# Balancing_V3.net
KiCad netlist of a schematic drawn in EAGLE
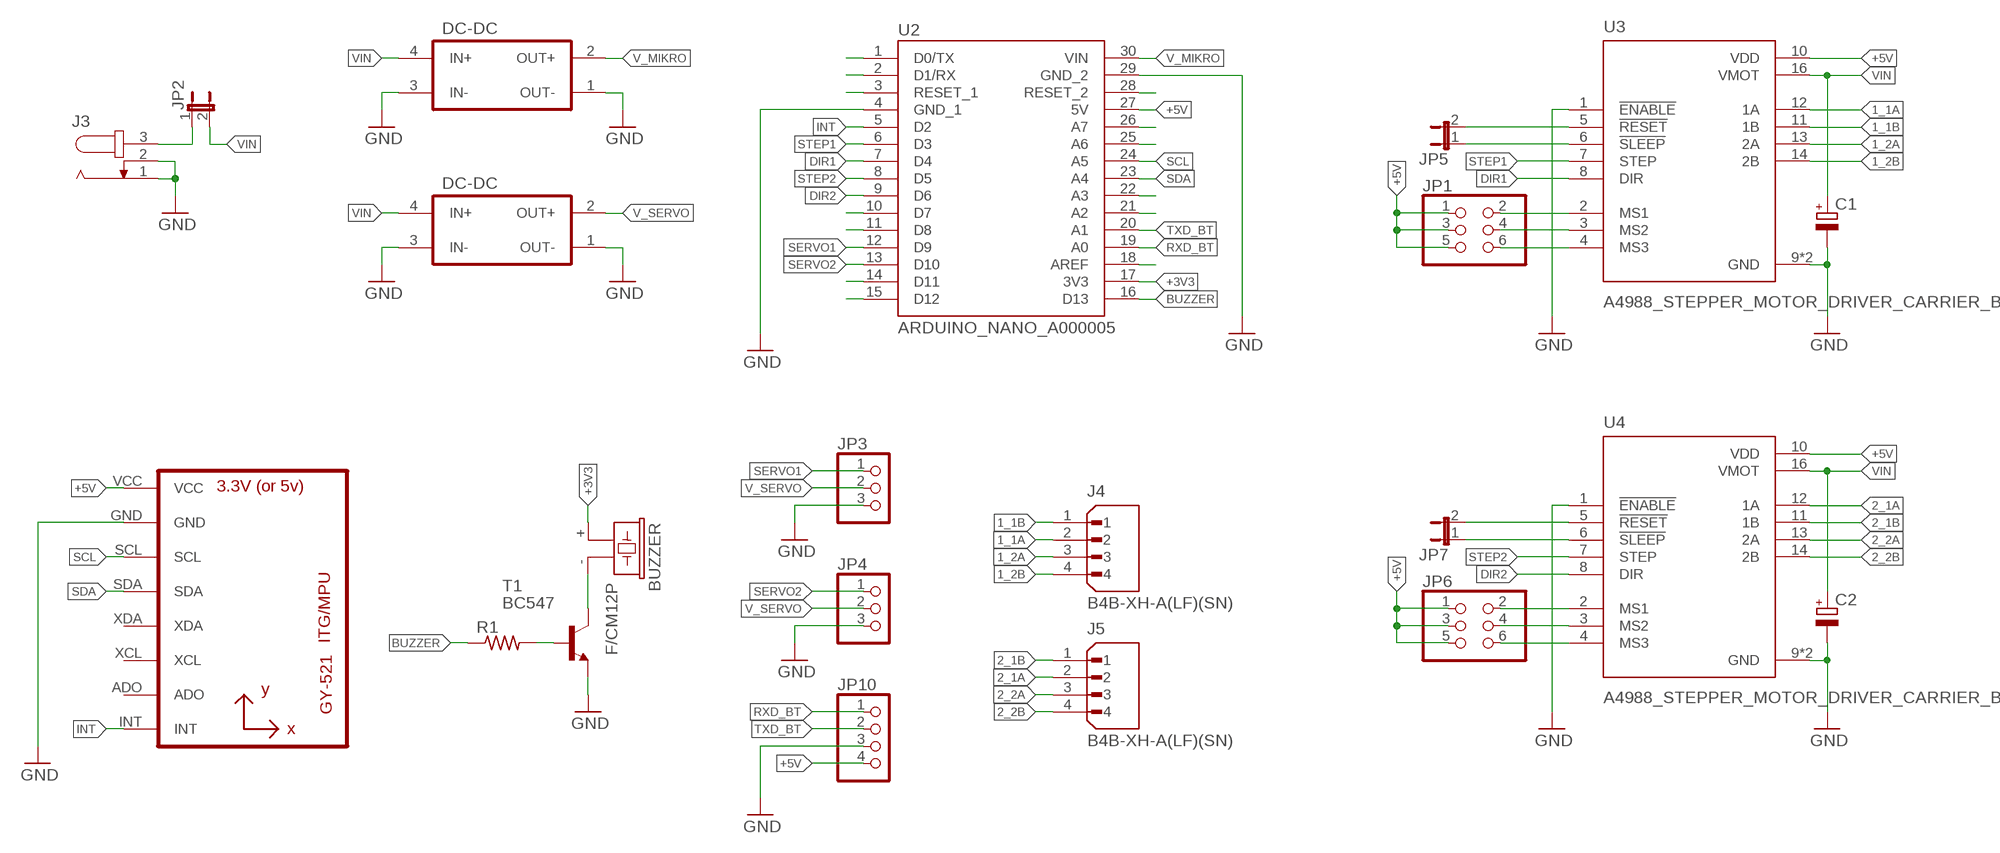
[diagram p0: schematic, sheet 1]

(export (version "E")
  (design (tool "Eeschema 10.0.6"))
  (components
    (comp (ref "BUZZER")
      (value "F/CM12P")
      (footprint "eagle-import:F_CM12P")
      (libsource (lib "eagle-import") (part "F/CM12P"))
    )
    (comp (ref "C1")
      (value "CPOL-EUE2.5-6")
      (footprint "eagle-import:E2,5-6")
      (libsource (lib "eagle-import") (part "CPOL-EUE2.5-6"))
    )
    (comp (ref "C2")
      (value "CPOL-EUE2.5-6")
      (footprint "eagle-import:E2,5-6")
      (libsource (lib "eagle-import") (part "CPOL-EUE2.5-6"))
    )
    (comp (ref "J3")
      (value "JACK-PLUG1")
      (footprint "eagle-import:SPC4078")
      (libsource (lib "eagle-import") (part "JACK-PLUG1"))
    )
    (comp (ref "J4")
      (value "B4B-XH-A(LF)(SN)")
      (footprint "eagle-import:JST_B4B-XH-A(LF)(SN)")
      (fields (field (name "MF") "JST") (field (name "MP") "B4B-XH-A  (LF)(SN)"))
      (libsource (lib "eagle-import") (part "B4B-XH-A(LF)(SN)"))
    )
    (comp (ref "J5")
      (value "B4B-XH-A(LF)(SN)")
      (footprint "eagle-import:JST_B4B-XH-A(LF)(SN)")
      (fields (field (name "MF") "JST") (field (name "MP") "B4B-XH-A  (LF)(SN)"))
      (libsource (lib "eagle-import") (part "B4B-XH-A(LF)(SN)"))
    )
    (comp (ref "JP1")
      (value "PINHD-2X3")
      (footprint "eagle-import:2X03")
      (libsource (lib "eagle-import") (part "PINHD-2X3"))
    )
    (comp (ref "JP2")
      (value "JP1E")
      (footprint "eagle-import:JP1")
      (libsource (lib "eagle-import") (part "JP1E"))
    )
    (comp (ref "JP3")
      (value "PINHD-1X3")
      (footprint "eagle-import:1X03")
      (libsource (lib "eagle-import") (part "PINHD-1X3"))
    )
    (comp (ref "JP4")
      (value "PINHD-1X3")
      (footprint "eagle-import:1X03")
      (libsource (lib "eagle-import") (part "PINHD-1X3"))
    )
    (comp (ref "JP5")
      (value "JP1E")
      (footprint "eagle-import:JP1")
      (libsource (lib "eagle-import") (part "JP1E"))
    )
    (comp (ref "JP6")
      (value "PINHD-2X3")
      (footprint "eagle-import:2X03")
      (libsource (lib "eagle-import") (part "PINHD-2X3"))
    )
    (comp (ref "JP7")
      (value "JP1E")
      (footprint "eagle-import:JP1")
      (libsource (lib "eagle-import") (part "JP1E"))
    )
    (comp (ref "JP10")
      (value "PINHD-1X4")
      (footprint "eagle-import:1X04")
      (libsource (lib "eagle-import") (part "PINHD-1X4"))
    )
    (comp (ref "R1")
      (value "R-US_0204/7")
      (footprint "eagle-import:0204_7")
      (libsource (lib "eagle-import") (part "R-US_0204/7"))
    )
    (comp (ref "T1")
      (value "BC547")
      (footprint "eagle-import:TO92")
      (libsource (lib "eagle-import") (part "BC547"))
    )
    (comp (ref "U$1")
      (value "DC-DC_CONV")
      (footprint "eagle-import:DC-DC_CONV")
      (libsource (lib "eagle-import") (part "DC-DC_CONV"))
    )
    (comp (ref "U$2")
      (value "DC-DC_CONV")
      (footprint "eagle-import:DC-DC_CONV")
      (libsource (lib "eagle-import") (part "DC-DC_CONV"))
    )
    (comp (ref "U1")
      (value "GY-521MPU6050")
      (footprint "eagle-import:GY-521")
      (libsource (lib "eagle-import") (part "GY-521MPU6050"))
    )
    (comp (ref "U2")
      (value "ARDUINO_NANO_A000005")
      (footprint "eagle-import:MODULE_ARDUINO_NANO_A000005")
      (fields (field (name "MF") "Arduino") (field (name "MP") "ARDUINO NANO A000005"))
      (libsource (lib "eagle-import") (part "ARDUINO_NANO_A000005"))
    )
    (comp (ref "U3")
      (value "A4988_STEPPER_MOTOR_DRIVER_CARRIER_BLACK")
      (footprint "eagle-import:MODULE_A4988_STEPPER_MOTOR_DRIVER_CARRIER_BLACK")
      (fields (field (name "MF") "Pololu") (field (name "MP") "A4988 STEPPER MOTOR DRIVER CARRIER BLACK"))
      (libsource (lib "eagle-import") (part "A4988_STEPPER_MOTOR_DRIVER_CARRIER_BLACK"))
    )
    (comp (ref "U4")
      (value "A4988_STEPPER_MOTOR_DRIVER_CARRIER_BLACK")
      (footprint "eagle-import:MODULE_A4988_STEPPER_MOTOR_DRIVER_CARRIER_BLACK")
      (fields (field (name "MF") "Pololu") (field (name "MP") "A4988 STEPPER MOTOR DRIVER CARRIER BLACK"))
      (libsource (lib "eagle-import") (part "A4988_STEPPER_MOTOR_DRIVER_CARRIER_BLACK"))
    )
  )
  (nets
    (net (code "1") (name "+3V3") (class "Default")
      (node (ref "BUZZER") (pin "+") (pinfunction "1_+") (pintype "passive"))
      (node (ref "U2") (pin "17") (pinfunction "3V3_17") (pintype "power_in"))
    )
    (net (code "2") (name "+5V") (class "Default")
      (node (ref "JP1") (pin "1") (pinfunction "1_1") (pintype "passive"))
      (node (ref "JP1") (pin "3") (pinfunction "3_3") (pintype "passive"))
      (node (ref "JP1") (pin "5") (pinfunction "5_5") (pintype "passive"))
      (node (ref "JP10") (pin "4") (pinfunction "4_4") (pintype "passive"))
      (node (ref "JP6") (pin "1") (pinfunction "1_1") (pintype "passive"))
      (node (ref "JP6") (pin "3") (pinfunction "3_3") (pintype "passive"))
      (node (ref "JP6") (pin "5") (pinfunction "5_5") (pintype "passive"))
      (node (ref "U1") (pin "VCC") (pinfunction "VCC_VCC") (pintype "bidirectional"))
      (node (ref "U2") (pin "27") (pinfunction "5V_27") (pintype "power_in"))
      (node (ref "U3") (pin "10") (pinfunction "VDD_10") (pintype "power_in"))
      (node (ref "U4") (pin "10") (pinfunction "VDD_10") (pintype "power_in"))
    )
    (net (code "3") (name "1_1A") (class "Default")
      (node (ref "J4") (pin "2") (pinfunction "2_2") (pintype "passive"))
      (node (ref "U3") (pin "12") (pinfunction "1A_12") (pintype "output"))
    )
    (net (code "4") (name "1_1B") (class "Default")
      (node (ref "J4") (pin "1") (pinfunction "1_1") (pintype "passive"))
      (node (ref "U3") (pin "11") (pinfunction "1B_11") (pintype "output"))
    )
    (net (code "5") (name "1_2A") (class "Default")
      (node (ref "J4") (pin "3") (pinfunction "3_3") (pintype "passive"))
      (node (ref "U3") (pin "13") (pinfunction "2A_13") (pintype "output"))
    )
    (net (code "6") (name "1_2B") (class "Default")
      (node (ref "J4") (pin "4") (pinfunction "4_4") (pintype "passive"))
      (node (ref "U3") (pin "14") (pinfunction "2B_14") (pintype "output"))
    )
    (net (code "7") (name "2_1A") (class "Default")
      (node (ref "J5") (pin "2") (pinfunction "2_2") (pintype "passive"))
      (node (ref "U4") (pin "12") (pinfunction "1A_12") (pintype "output"))
    )
    (net (code "8") (name "2_1B") (class "Default")
      (node (ref "J5") (pin "1") (pinfunction "1_1") (pintype "passive"))
      (node (ref "U4") (pin "11") (pinfunction "1B_11") (pintype "output"))
    )
    (net (code "9") (name "2_2A") (class "Default")
      (node (ref "J5") (pin "3") (pinfunction "3_3") (pintype "passive"))
      (node (ref "U4") (pin "13") (pinfunction "2A_13") (pintype "output"))
    )
    (net (code "10") (name "2_2B") (class "Default")
      (node (ref "J5") (pin "4") (pinfunction "4_4") (pintype "passive"))
      (node (ref "U4") (pin "14") (pinfunction "2B_14") (pintype "output"))
    )
    (net (code "11") (name "BUZZER") (class "Default")
      (node (ref "R1") (pin "1") (pinfunction "1_1") (pintype "passive"))
      (node (ref "U2") (pin "16") (pinfunction "D13_16") (pintype "bidirectional"))
    )
    (net (code "12") (name "DIR1") (class "Default")
      (node (ref "U2") (pin "7") (pinfunction "D4_7") (pintype "bidirectional"))
      (node (ref "U3") (pin "8") (pinfunction "DIR_8") (pintype "input"))
    )
    (net (code "13") (name "DIR2") (class "Default")
      (node (ref "U2") (pin "9") (pinfunction "D6_9") (pintype "bidirectional"))
      (node (ref "U4") (pin "8") (pinfunction "DIR_8") (pintype "input"))
    )
    (net (code "14") (name "GND") (class "Default")
      (node (ref "C1") (pin "-") (pinfunction "-_-") (pintype "passive"))
      (node (ref "C2") (pin "-") (pinfunction "-_-") (pintype "passive"))
      (node (ref "J3") (pin "1") (pinfunction "1_1") (pintype "passive"))
      (node (ref "J3") (pin "2") (pinfunction "2_2") (pintype "passive"))
      (node (ref "JP10") (pin "3") (pinfunction "3_3") (pintype "passive"))
      (node (ref "JP3") (pin "3") (pinfunction "3_3") (pintype "passive"))
      (node (ref "JP4") (pin "3") (pinfunction "3_3") (pintype "passive"))
      (node (ref "T1") (pin "1") (pinfunction "E_1") (pintype "passive"))
      (node (ref "U$1") (pin "1") (pinfunction "OUT-_1") (pintype "bidirectional"))
      (node (ref "U$1") (pin "3") (pinfunction "IN-_3") (pintype "bidirectional"))
      (node (ref "U$2") (pin "1") (pinfunction "OUT-_1") (pintype "bidirectional"))
      (node (ref "U$2") (pin "3") (pinfunction "IN-_3") (pintype "bidirectional"))
      (node (ref "U1") (pin "GND") (pinfunction "GND_GND") (pintype "bidirectional"))
      (node (ref "U2") (pin "29") (pinfunction "GND_2_29") (pintype "power_in"))
      (node (ref "U2") (pin "4") (pinfunction "GND_1_4") (pintype "power_in"))
      (node (ref "U3") (pin "1") (pinfunction "~{ENABLE}_1") (pintype "input"))
      (node (ref "U3") (pin "15") (pinfunction "GND_15") (pintype "power_in"))
      (node (ref "U3") (pin "9") (pinfunction "GND_9") (pintype "power_in"))
      (node (ref "U4") (pin "1") (pinfunction "~{ENABLE}_1") (pintype "input"))
      (node (ref "U4") (pin "15") (pinfunction "GND_15") (pintype "power_in"))
      (node (ref "U4") (pin "9") (pinfunction "GND_9") (pintype "power_in"))
    )
    (net (code "15") (name "INT") (class "Default")
      (node (ref "U1") (pin "INT") (pinfunction "INT_INT") (pintype "bidirectional"))
      (node (ref "U2") (pin "5") (pinfunction "D2_5") (pintype "bidirectional"))
    )
    (net (code "16") (name "Net-(BUZZER-2)") (class "Default")
      (node (ref "BUZZER") (pin "-") (pinfunction "2_-") (pintype "passive"))
      (node (ref "T1") (pin "3") (pinfunction "C_3") (pintype "passive"))
    )
    (net (code "17") (name "Net-(J3-Pad3)") (class "Default")
      (node (ref "J3") (pin "3") (pinfunction "3_3") (pintype "passive"))
      (node (ref "JP2") (pin "1") (pinfunction "1_1") (pintype "passive"))
    )
    (net (code "18") (name "Net-(T1-B)") (class "Default")
      (node (ref "R1") (pin "2") (pinfunction "2_2") (pintype "passive"))
      (node (ref "T1") (pin "2") (pinfunction "B_2") (pintype "passive"))
    )
    (net (code "19") (name "Net-(U3-MS1)") (class "Default")
      (node (ref "JP1") (pin "2") (pinfunction "2_2") (pintype "passive"))
      (node (ref "U3") (pin "2") (pinfunction "MS1_2") (pintype "input"))
    )
    (net (code "20") (name "Net-(U3-MS2)") (class "Default")
      (node (ref "JP1") (pin "4") (pinfunction "4_4") (pintype "passive"))
      (node (ref "U3") (pin "3") (pinfunction "MS2_3") (pintype "input"))
    )
    (net (code "21") (name "Net-(U3-MS3)") (class "Default")
      (node (ref "JP1") (pin "6") (pinfunction "6_6") (pintype "passive"))
      (node (ref "U3") (pin "4") (pinfunction "MS3_4") (pintype "input"))
    )
    (net (code "22") (name "Net-(U3-~{RESET})") (class "Default")
      (node (ref "JP5") (pin "2") (pinfunction "2_2") (pintype "passive"))
      (node (ref "U3") (pin "5") (pinfunction "~{RESET}_5") (pintype "input"))
    )
    (net (code "23") (name "Net-(U3-~{SLEEP})") (class "Default")
      (node (ref "JP5") (pin "1") (pinfunction "1_1") (pintype "passive"))
      (node (ref "U3") (pin "6") (pinfunction "~{SLEEP}_6") (pintype "input"))
    )
    (net (code "24") (name "Net-(U4-MS1)") (class "Default")
      (node (ref "JP6") (pin "2") (pinfunction "2_2") (pintype "passive"))
      (node (ref "U4") (pin "2") (pinfunction "MS1_2") (pintype "input"))
    )
    (net (code "25") (name "Net-(U4-MS2)") (class "Default")
      (node (ref "JP6") (pin "4") (pinfunction "4_4") (pintype "passive"))
      (node (ref "U4") (pin "3") (pinfunction "MS2_3") (pintype "input"))
    )
    (net (code "26") (name "Net-(U4-MS3)") (class "Default")
      (node (ref "JP6") (pin "6") (pinfunction "6_6") (pintype "passive"))
      (node (ref "U4") (pin "4") (pinfunction "MS3_4") (pintype "input"))
    )
    (net (code "27") (name "Net-(U4-~{RESET})") (class "Default")
      (node (ref "JP7") (pin "2") (pinfunction "2_2") (pintype "passive"))
      (node (ref "U4") (pin "5") (pinfunction "~{RESET}_5") (pintype "input"))
    )
    (net (code "28") (name "Net-(U4-~{SLEEP})") (class "Default")
      (node (ref "JP7") (pin "1") (pinfunction "1_1") (pintype "passive"))
      (node (ref "U4") (pin "6") (pinfunction "~{SLEEP}_6") (pintype "input"))
    )
    (net (code "29") (name "RXD_BT") (class "Default")
      (node (ref "JP10") (pin "1") (pinfunction "1_1") (pintype "passive"))
      (node (ref "U2") (pin "19") (pinfunction "A0_19") (pintype "input"))
    )
    (net (code "30") (name "SCL") (class "Default")
      (node (ref "U1") (pin "SCL") (pinfunction "SCL_SCL") (pintype "bidirectional"))
      (node (ref "U2") (pin "24") (pinfunction "A5_24") (pintype "input"))
    )
    (net (code "31") (name "SDA") (class "Default")
      (node (ref "U1") (pin "SDA") (pinfunction "SDA_SDA") (pintype "bidirectional"))
      (node (ref "U2") (pin "23") (pinfunction "A4_23") (pintype "input"))
    )
    (net (code "32") (name "SERVO1") (class "Default")
      (node (ref "JP3") (pin "1") (pinfunction "1_1") (pintype "passive"))
      (node (ref "U2") (pin "12") (pinfunction "D9_12") (pintype "bidirectional"))
    )
    (net (code "33") (name "SERVO2") (class "Default")
      (node (ref "JP4") (pin "1") (pinfunction "1_1") (pintype "passive"))
      (node (ref "U2") (pin "13") (pinfunction "D10_13") (pintype "bidirectional"))
    )
    (net (code "34") (name "STEP1") (class "Default")
      (node (ref "U2") (pin "6") (pinfunction "D3_6") (pintype "bidirectional"))
      (node (ref "U3") (pin "7") (pinfunction "STEP_7") (pintype "input"))
    )
    (net (code "35") (name "STEP2") (class "Default")
      (node (ref "U2") (pin "8") (pinfunction "D5_8") (pintype "bidirectional"))
      (node (ref "U4") (pin "7") (pinfunction "STEP_7") (pintype "input"))
    )
    (net (code "36") (name "TXD_BT") (class "Default")
      (node (ref "JP10") (pin "2") (pinfunction "2_2") (pintype "passive"))
      (node (ref "U2") (pin "20") (pinfunction "A1_20") (pintype "input"))
    )
    (net (code "37") (name "VIN") (class "Default")
      (node (ref "C1") (pin "+") (pinfunction "+_+") (pintype "passive"))
      (node (ref "C2") (pin "+") (pinfunction "+_+") (pintype "passive"))
      (node (ref "JP2") (pin "2") (pinfunction "2_2") (pintype "passive"))
      (node (ref "U$1") (pin "4") (pinfunction "IN+_4") (pintype "bidirectional"))
      (node (ref "U$2") (pin "4") (pinfunction "IN+_4") (pintype "bidirectional"))
      (node (ref "U3") (pin "16") (pinfunction "VMOT_16") (pintype "power_in"))
      (node (ref "U4") (pin "16") (pinfunction "VMOT_16") (pintype "power_in"))
    )
    (net (code "38") (name "V_MIKRO") (class "Default")
      (node (ref "U$1") (pin "2") (pinfunction "OUT+_2") (pintype "bidirectional"))
      (node (ref "U2") (pin "30") (pinfunction "VIN_30") (pintype "power_in"))
    )
    (net (code "39") (name "V_SERVO") (class "Default")
      (node (ref "JP3") (pin "2") (pinfunction "2_2") (pintype "passive"))
      (node (ref "JP4") (pin "2") (pinfunction "2_2") (pintype "passive"))
      (node (ref "U$2") (pin "2") (pinfunction "OUT+_2") (pintype "bidirectional"))
    )
    (net (code "40") (name "unconnected-(U1-PadADO)") (class "Default")
      (node (ref "U1") (pin "ADO") (pinfunction "ADO_ADO") (pintype "bidirectional"))
    )
    (net (code "41") (name "unconnected-(U1-PadXCL)") (class "Default")
      (node (ref "U1") (pin "XCL") (pinfunction "XCL_XCL") (pintype "bidirectional"))
    )
    (net (code "42") (name "unconnected-(U1-PadXDA)") (class "Default")
      (node (ref "U1") (pin "XDA") (pinfunction "XDA_XDA") (pintype "bidirectional"))
    )
    (net (code "43") (name "unconnected-(U2-A2-Pad21)") (class "Default")
      (node (ref "U2") (pin "21") (pinfunction "A2_21") (pintype "input"))
    )
    (net (code "44") (name "unconnected-(U2-A3-Pad22)") (class "Default")
      (node (ref "U2") (pin "22") (pinfunction "A3_22") (pintype "input"))
    )
    (net (code "45") (name "unconnected-(U2-A6-Pad25)") (class "Default")
      (node (ref "U2") (pin "25") (pinfunction "A6_25") (pintype "input"))
    )
    (net (code "46") (name "unconnected-(U2-A7-Pad26)") (class "Default")
      (node (ref "U2") (pin "26") (pinfunction "A7_26") (pintype "input"))
    )
    (net (code "47") (name "unconnected-(U2-AREF-Pad18)") (class "Default")
      (node (ref "U2") (pin "18") (pinfunction "AREF_18") (pintype "input"))
    )
    (net (code "48") (name "unconnected-(U2-D0{slash}TX-Pad1)") (class "Default")
      (node (ref "U2") (pin "1") (pinfunction "D0/TX_1") (pintype "bidirectional"))
    )
    (net (code "49") (name "unconnected-(U2-D1{slash}RX-Pad2)") (class "Default")
      (node (ref "U2") (pin "2") (pinfunction "D1/RX_2") (pintype "bidirectional"))
    )
    (net (code "50") (name "unconnected-(U2-D7-Pad10)") (class "Default")
      (node (ref "U2") (pin "10") (pinfunction "D7_10") (pintype "bidirectional"))
    )
    (net (code "51") (name "unconnected-(U2-D8-Pad11)") (class "Default")
      (node (ref "U2") (pin "11") (pinfunction "D8_11") (pintype "bidirectional"))
    )
    (net (code "52") (name "unconnected-(U2-D11-Pad14)") (class "Default")
      (node (ref "U2") (pin "14") (pinfunction "D11_14") (pintype "bidirectional"))
    )
    (net (code "53") (name "unconnected-(U2-D12-Pad15)") (class "Default")
      (node (ref "U2") (pin "15") (pinfunction "D12_15") (pintype "bidirectional"))
    )
    (net (code "54") (name "unconnected-(U2-RESET_1-Pad3)") (class "Default")
      (node (ref "U2") (pin "3") (pinfunction "RESET_1_3") (pintype "input"))
    )
    (net (code "55") (name "unconnected-(U2-RESET_2-Pad28)") (class "Default")
      (node (ref "U2") (pin "28") (pinfunction "RESET_2_28") (pintype "input"))
    )
  )
)
